# LM399_ASCII.net
KiCad netlist of a schematic drawn in Altium Designer
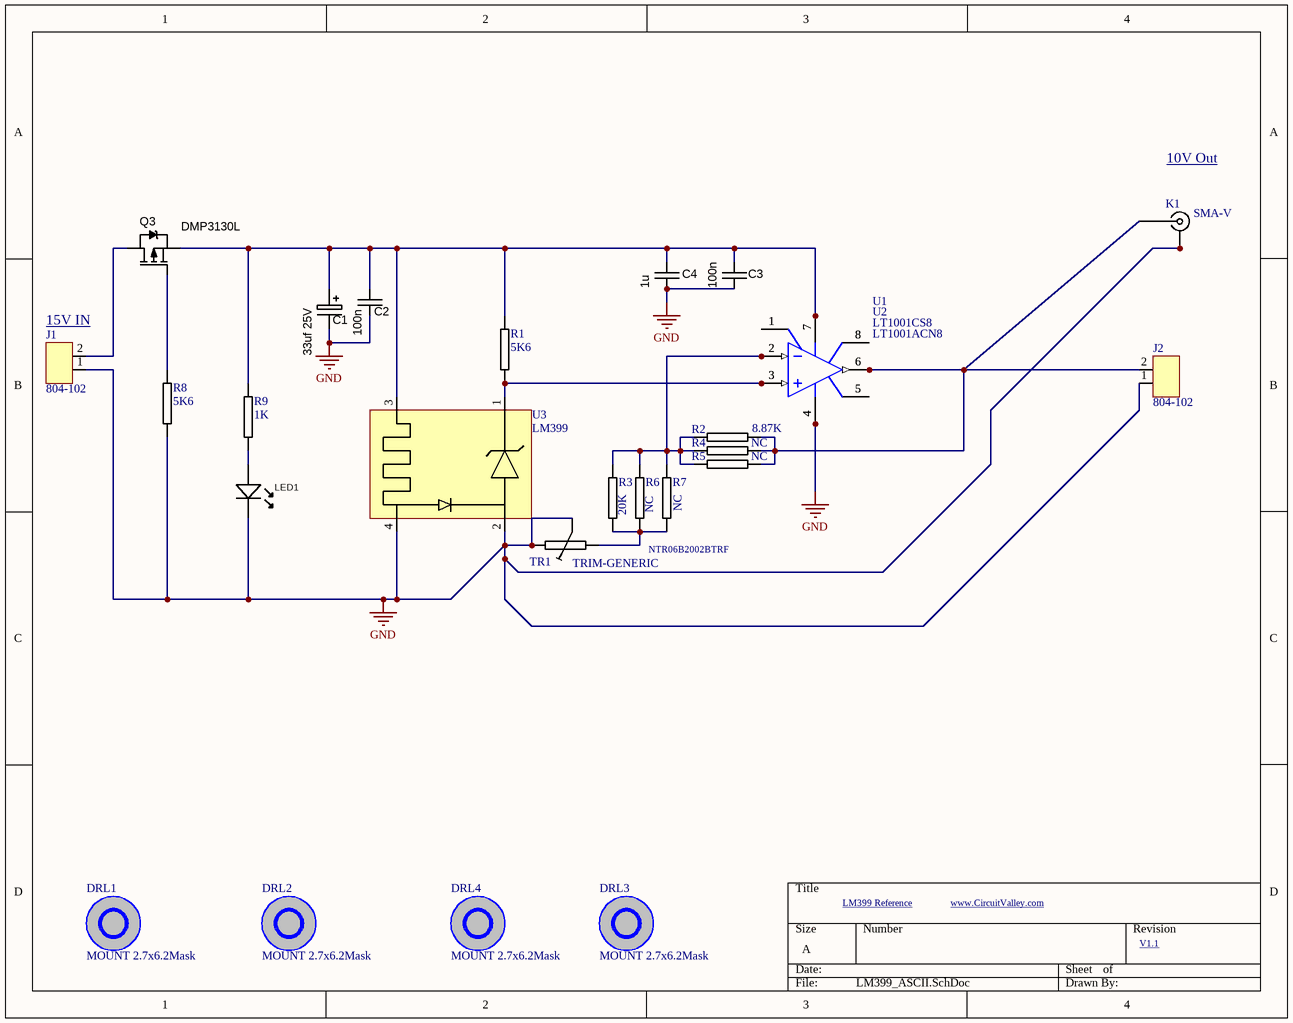
[diagram p0: LM399_ASCII.SchDoc]

(export (version "E")
  (design (tool "Eeschema 10.0.6"))
  (components
    (comp (ref "C1")
      (value "33uf 25V")
      (footprint "CAPMP7343X310N")
      (description "Capacitor SMD Tant 330uF 20% 6V3 2917")
      (fields
        (field (name "TOLERANCE") "±20%")
        (field (name "MANUFACTURER PART NUMBER") "T520D337M006ATE015")
      )
      (libsource (lib "PBL - Capacitors") (part "CAPT_330u_2917_6V3"))
    )
    (comp (ref "C2")
      (value "100n")
      (footprint "CAPC1608N")
      (description "Capacitor SMD Cer 10pF 5% 50V NP0 0603")
      (fields (field (name "TOLERANCE") "±5%") (field (name "PART") "C0603X104K5RAC"))
      (libsource (lib "PBL - Capacitors") (part "CAPC_10p_0603_NP0_1%_50V"))
    )
    (comp (ref "C3")
      (value "100n")
      (footprint "CAPC1608N")
      (description "Capacitor SMD Cer 10pF 5% 50V NP0 0603")
      (fields (field (name "PART") "C0603X104K5RAC"))
      (libsource (lib "PBL - Capacitors") (part "CAPC_10p_0603_NP0_1%_50V"))
    )
    (comp (ref "C4")
      (value "1u")
      (footprint "CAPC1608N")
      (description "Capacitor SMD Cer 10pF 5% 50V NP0 0603")
      (fields (field (name "TOLERANCE") "±5%") (field (name "PART") "C0603X104K5RAC"))
      (libsource (lib "PBL - Capacitors") (part "CAPC_10p_0603_NP0_1%_50V"))
    )
    (comp (ref "DRL1")
      (value "MOUNT 2.7x6.2Mask")
      (footprint "NO_COPPER_NOMASK_2m75_6m2")
      (libsource (lib "mounting_hole") (part "DRILL_2.7x6.2Mask_NOCOPPER"))
    )
    (comp (ref "DRL2")
      (value "MOUNT 2.7x6.2Mask")
      (footprint "NO_COPPER_NOMASK_2m75_6m2")
      (libsource (lib "mounting_hole") (part "DRILL_2.7x6.2Mask_NOCOPPER"))
    )
    (comp (ref "DRL3")
      (value "MOUNT 2.7x6.2Mask")
      (footprint "NO_COPPER_NOMASK_2m75_6m2")
      (libsource (lib "mounting_hole") (part "DRILL_2.7x6.2Mask_NOCOPPER"))
    )
    (comp (ref "DRL4")
      (value "MOUNT 2.7x6.2Mask")
      (footprint "NO_COPPER_NOMASK_2m75_6m2")
      (libsource (lib "mounting_hole") (part "DRILL_2.7x6.2Mask_NOCOPPER"))
    )
    (comp (ref "J1") (value "804-102") (footprint "804-102") (libsource (lib "") (part "804-102_1")))
    (comp (ref "J2") (value "804-102") (footprint "804-102") (libsource (lib "cvlib") (part "804-102")))
    (comp (ref "K1")
      (value "SMA-V")
      (footprint "SMA-V")
      (description "SMA THREADED RF CONNECTOR VERTICAL")
      (libsource (lib "Generic") (part "SMA-V"))
    )
    (comp (ref "LED1")
      (value "~")
      (footprint "LED-0805-K")
      (description "LED, 0805 SMD, Green")
      (libsource (lib "PBL - Light Sources") (part "LED_SMD_Green_0805"))
    )
    (comp (ref "Q3")
      (value "DMP3130L")
      (footprint "SOT23-3")
      (description "MOSFET SMD P-CH 50V 130mA SOT23-3")
      (libsource (lib "PBL - Transistors") (part "MOSFET_BSS84"))
    )
    (comp (ref "R1")
      (value "5K6")
      (footprint "0603R-GENERIC")
      (description "GENERIC RESISTOR 0603")
      (fields (field (name "PART") "RMCF0603JT7K50"))
      (libsource (lib "Generic") (part "0603R-7K5"))
    )
    (comp (ref "R2")
      (value "8.87K")
      (footprint "0603R-TBD")
      (description "RESISTOR 0603 VALUE TO BE DETERMINED")
      (fields (field (name "PART") "RN73C1J8K87BTG"))
      (libsource (lib "Generic") (part "0603R-TBD"))
    )
    (comp (ref "R3")
      (value "20K")
      (footprint "0603R-GENERIC")
      (description "GENERIC RESISTOR 0603")
      (fields (field (name "PART") "ERA-3ARW203V"))
      (libsource (lib "Generic") (part "0603R-20K"))
    )
    (comp (ref "R4")
      (value "NC")
      (footprint "0603R-TBD")
      (description "RESISTOR 0603 VALUE TO BE DETERMINED")
      (fields (field (name "PART") "RN73C1J8K87BTG"))
      (libsource (lib "Generic") (part "0603R-TBD"))
    )
    (comp (ref "R5")
      (value "NC")
      (footprint "0603R-TBD")
      (description "RESISTOR 0603 VALUE TO BE DETERMINED")
      (fields (field (name "PART") "RN73C1J8K87BTG"))
      (libsource (lib "Generic") (part "0603R-TBD"))
    )
    (comp (ref "R6")
      (value "NC")
      (footprint "0603R-GENERIC")
      (description "GENERIC RESISTOR 0603")
      (fields (field (name "PART") "ERA-3ARW203V"))
      (libsource (lib "Generic") (part "0603R-20K"))
    )
    (comp (ref "R7")
      (value "NC")
      (footprint "0603R-GENERIC")
      (description "GENERIC RESISTOR 0603")
      (fields (field (name "PART") "ERA-3ARW203V"))
      (libsource (lib "Generic") (part "0603R-20K"))
    )
    (comp (ref "R8")
      (value "5K6")
      (footprint "0603R-GENERIC")
      (description "GENERIC RESISTOR 0603")
      (fields (field (name "PART") "RMCF0603JT7K50"))
      (libsource (lib "Generic") (part "0603R-7K5"))
    )
    (comp (ref "R9")
      (value "1K")
      (footprint "0603R-120K")
      (description "GENERIC RESISTOR 0603")
      (fields
        (field (name "MANUFACTURER") "Stackpole Electronics Inc")
        (field (name "MANUFACTURER PART NUMBER") "RMCF 1/16 120K 1% R")
      )
      (libsource (lib "Generic") (part "0603R-120K"))
    )
    (comp (ref "TR1")
      (value "TRIM-GENERIC")
      (footprint "TRIMMER-MT")
      (description "TRIMMABLE RESISTOR")
      (libsource (lib "Generic") (part "THTRIM-GENERIC"))
    )
    (comp (ref "U1")
      (value "LT1001CS8")
      (footprint "S8_N")
      (description "General Purpose, High Precision Op Amp")
      (fields (field (name "PART") "LT100ACN8"))
      (libsource (lib "LT Operational Amplifier") (part "LT1001CS8"))
    )
    (comp (ref "U2")
      (value "LT1001ACN8")
      (footprint "N8")
      (description "General Purpose, High Precision Op Amp")
      (fields (field (name "PUBLISHER") "Altium Limited"))
      (libsource (lib "LT Operational Amplifier") (part "LT1001ACN8"))
    )
    (comp (ref "U3") (value "LM399") (footprint "TO-46") (libsource (lib "cvlib") (part "LM399")))
  )
  (nets
    (net (code "1") (name "GND") (class "Default")
      (node (ref "C1") (pin "2") (pintype "passive"))
      (node (ref "C2") (pin "1") (pintype "passive"))
      (node (ref "C3") (pin "1") (pintype "passive"))
      (node (ref "C4") (pin "1") (pintype "passive"))
      (node (ref "J1") (pin "1") (pinfunction "PW_1") (pintype "passive"))
      (node (ref "J2") (pin "1") (pinfunction "PW_1") (pintype "passive"))
      (node (ref "K1") (pin "2") (pinfunction "2_2") (pintype "passive"))
      (node (ref "K1") (pin "3") (pinfunction "3_3") (pintype "passive"))
      (node (ref "K1") (pin "4") (pinfunction "4_4") (pintype "passive"))
      (node (ref "K1") (pin "5") (pinfunction "5_5") (pintype "passive"))
      (node (ref "LED1") (pin "K") (pinfunction "K_K") (pintype "passive"))
      (node (ref "R8") (pin "2") (pintype "passive"))
      (node (ref "TR1") (pin "2") (pinfunction "2_2") (pintype "passive"))
      (node (ref "TR1") (pin "W") (pinfunction "W_W") (pintype "passive"))
      (node (ref "U1") (pin "4") (pinfunction "V-_4") (pintype "power_in"))
      (node (ref "U2") (pin "4") (pinfunction "V-_4") (pintype "power_in"))
      (node (ref "U3") (pin "2") (pinfunction "D2_2") (pintype "passive"))
      (node (ref "U3") (pin "4") (pinfunction "H2_4") (pintype "passive"))
    )
    (net (code "2") (name "Net-(LED1-PadA)") (class "Default")
      (node (ref "LED1") (pin "A") (pinfunction "A_A") (pintype "passive"))
      (node (ref "R9") (pin "2") (pintype "passive"))
    )
    (net (code "3") (name "Net-(Q3-D)") (class "Default")
      (node (ref "J1") (pin "2") (pinfunction "PW_2") (pintype "passive"))
      (node (ref "Q3") (pin "3") (pinfunction "D_3") (pintype "passive"))
    )
    (net (code "4") (name "Net-(Q3-G)") (class "Default")
      (node (ref "Q3") (pin "1") (pinfunction "G_1") (pintype "passive"))
      (node (ref "R8") (pin "1") (pintype "passive"))
    )
    (net (code "5") (name "Net-(Q3-S)") (class "Default")
      (node (ref "C1") (pin "1") (pintype "passive"))
      (node (ref "C2") (pin "2") (pintype "passive"))
      (node (ref "C3") (pin "2") (pintype "passive"))
      (node (ref "C4") (pin "2") (pintype "passive"))
      (node (ref "Q3") (pin "2") (pinfunction "S_2") (pintype "passive"))
      (node (ref "R1") (pin "1") (pintype "passive"))
      (node (ref "R9") (pin "1") (pintype "passive"))
      (node (ref "U1") (pin "7") (pinfunction "V+_7") (pintype "power_in"))
      (node (ref "U2") (pin "7") (pinfunction "V+_7") (pintype "power_in"))
      (node (ref "U3") (pin "3") (pinfunction "H1_3") (pintype "passive"))
    )
    (net (code "6") (name "Net-(R3-Pad1)") (class "Default")
      (node (ref "R3") (pin "1") (pintype "passive"))
      (node (ref "R6") (pin "1") (pintype "passive"))
      (node (ref "R7") (pin "1") (pintype "passive"))
      (node (ref "TR1") (pin "1") (pinfunction "1_1") (pintype "passive"))
    )
    (net (code "7") (name "Net-(U1-IN+)") (class "Default")
      (node (ref "R1") (pin "2") (pintype "passive"))
      (node (ref "U1") (pin "3") (pinfunction "IN+_3") (pintype "input"))
      (node (ref "U2") (pin "3") (pinfunction "IN+_3") (pintype "input"))
      (node (ref "U3") (pin "1") (pinfunction "D1_1") (pintype "passive"))
    )
    (net (code "8") (name "Net-(U1-IN-)") (class "Default")
      (node (ref "R2") (pin "1") (pintype "passive"))
      (node (ref "R3") (pin "2") (pintype "passive"))
      (node (ref "R4") (pin "1") (pintype "passive"))
      (node (ref "R5") (pin "1") (pintype "passive"))
      (node (ref "R6") (pin "2") (pintype "passive"))
      (node (ref "R7") (pin "2") (pintype "passive"))
      (node (ref "U1") (pin "2") (pinfunction "IN-_2") (pintype "input"))
      (node (ref "U2") (pin "2") (pinfunction "IN-_2") (pintype "input"))
    )
    (net (code "9") (name "Net-(U1-NC)") (class "Default")
      (node (ref "U1") (pin "5") (pinfunction "NC_5") (pintype "passive"))
      (node (ref "U2") (pin "5") (pinfunction "NC_5") (pintype "passive"))
    )
    (net (code "10") (name "Net-(U1-OUT)") (class "Default")
      (node (ref "J2") (pin "2") (pinfunction "PW_2") (pintype "passive"))
      (node (ref "K1") (pin "1") (pinfunction "1_1") (pintype "passive"))
      (node (ref "R2") (pin "2") (pintype "passive"))
      (node (ref "R4") (pin "2") (pintype "passive"))
      (node (ref "R5") (pin "2") (pintype "passive"))
      (node (ref "U1") (pin "6") (pinfunction "OUT_6") (pintype "output"))
      (node (ref "U2") (pin "6") (pinfunction "OUT_6") (pintype "output"))
    )
    (net (code "11") (name "Net-(U1-VOSTRIM-Pad1)") (class "Default")
      (node (ref "U1") (pin "1") (pinfunction "VOSTRIM_1") (pintype "passive"))
      (node (ref "U2") (pin "1") (pinfunction "VOSTRIM_1") (pintype "passive"))
    )
    (net (code "12") (name "Net-(U1-VOSTRIM-Pad8)") (class "Default")
      (node (ref "U1") (pin "8") (pinfunction "VOSTRIM_8") (pintype "passive"))
      (node (ref "U2") (pin "8") (pinfunction "VOSTRIM_8") (pintype "passive"))
    )
  )
)
